# LAUNCHXL-F28377S_1.net
KiCad netlist of a schematic drawn in Altium Designer
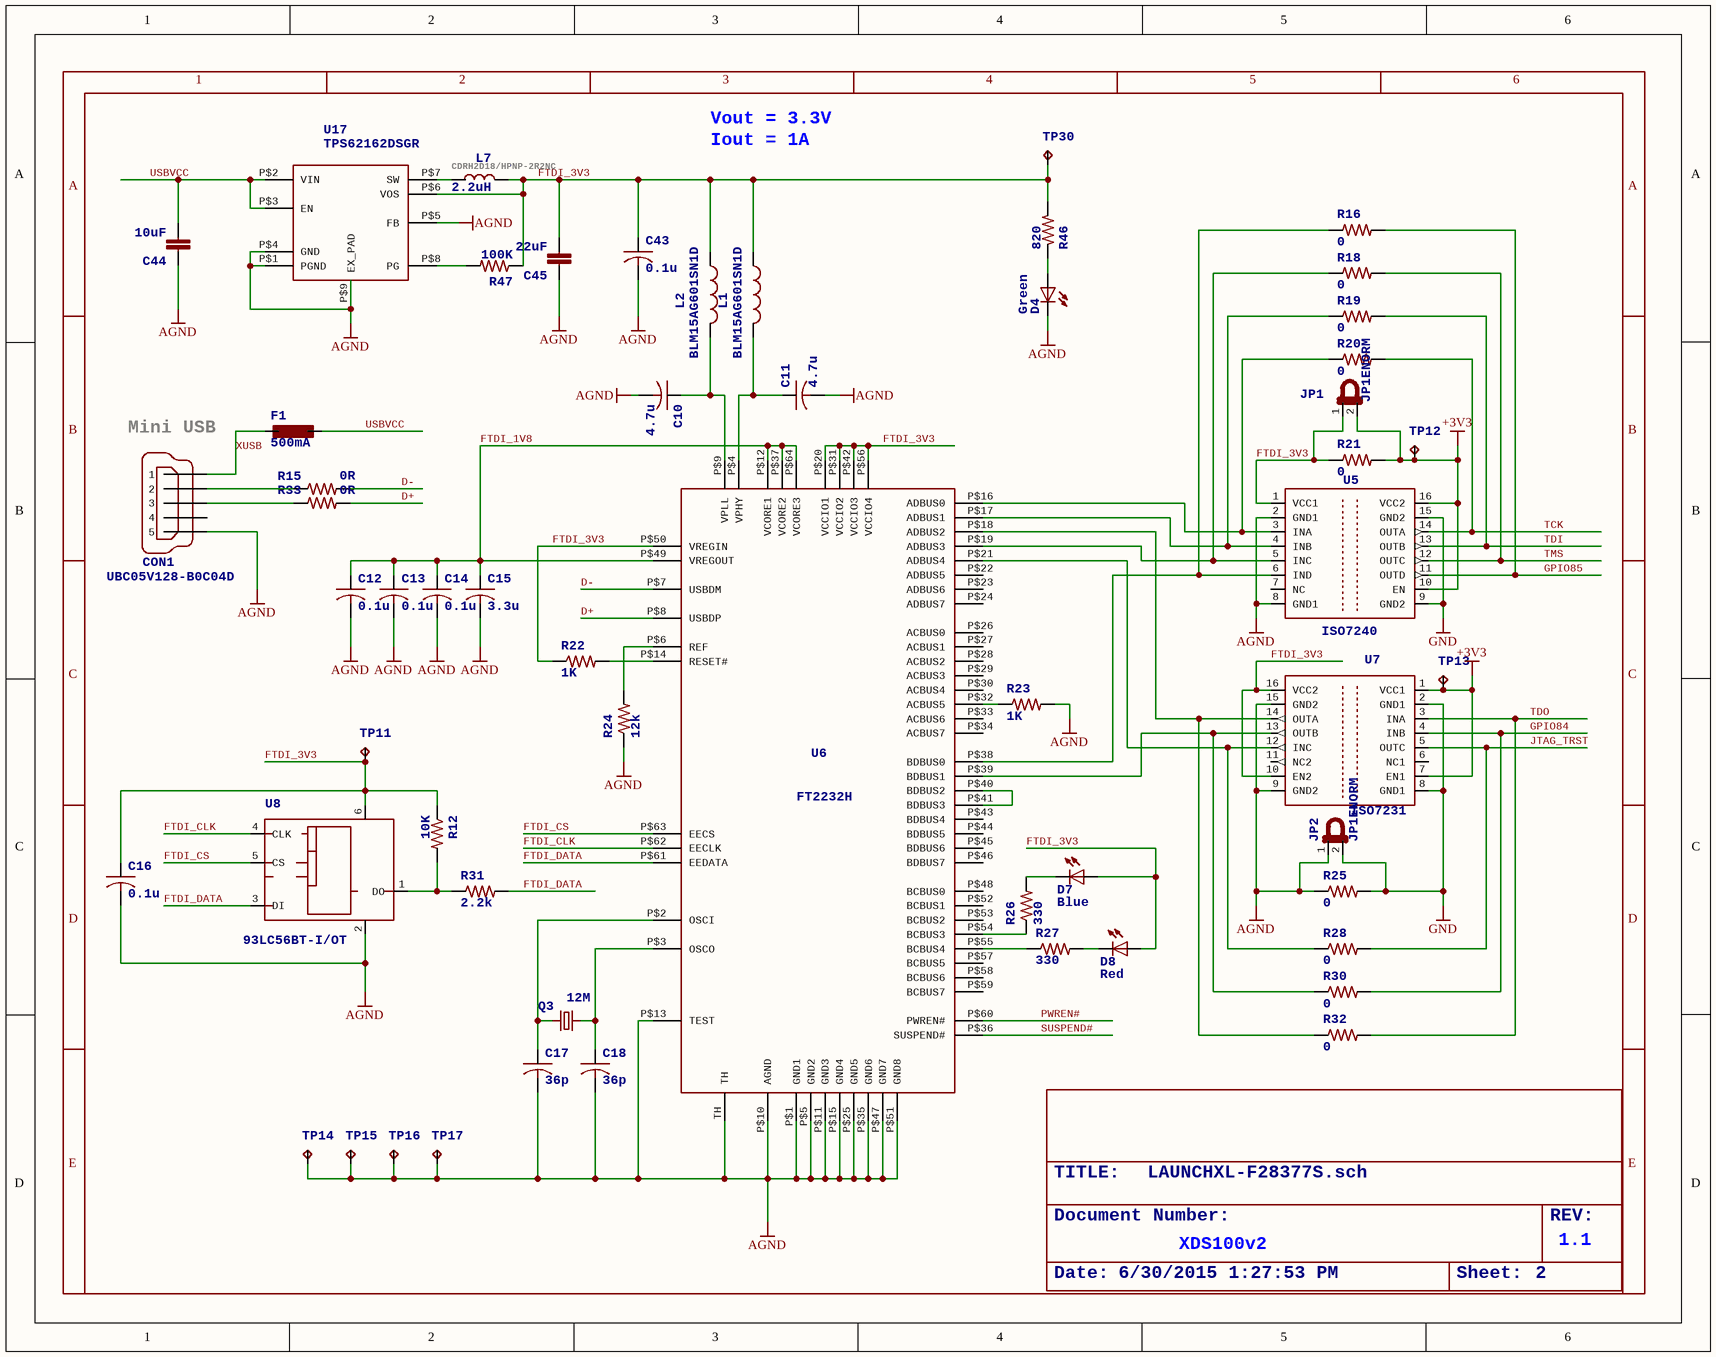
[diagram p0: LAUNCHXL-F28377S_1.SchDoc]

(export (version "E")
  (design (tool "Eeschema 10.0.6"))
  (components
    (comp (ref "C10")
      (value "4.7u")
      (footprint "C0402")
      (description "<B>CAPACITOR</B>, American symbol")
      (libsource (lib "rcl") (part "C-USC0402"))
    )
    (comp (ref "C11")
      (value "4.7u")
      (footprint "C0402")
      (description "<B>CAPACITOR</B>, American symbol")
      (libsource (lib "rcl") (part "C-USC0402"))
    )
    (comp (ref "C12")
      (value "0.1u")
      (footprint "C0402")
      (description "<B>CAPACITOR</B>, American symbol")
      (libsource (lib "rcl") (part "C-USC0402"))
    )
    (comp (ref "C13")
      (value "0.1u")
      (footprint "C0402")
      (description "<B>CAPACITOR</B>, American symbol")
      (libsource (lib "rcl") (part "C-USC0402"))
    )
    (comp (ref "C14")
      (value "0.1u")
      (footprint "C0402")
      (description "<B>CAPACITOR</B>, American symbol")
      (libsource (lib "rcl") (part "C-USC0402"))
    )
    (comp (ref "C15")
      (value "3.3u")
      (footprint "C0402")
      (description "<B>CAPACITOR</B>, American symbol")
      (libsource (lib "rcl") (part "C-USC0402"))
    )
    (comp (ref "C16")
      (value "0.1u")
      (footprint "C0402")
      (description "<B>CAPACITOR</B>, American symbol")
      (libsource (lib "rcl") (part "C-USC0402"))
    )
    (comp (ref "C17")
      (value "36p")
      (footprint "C0402")
      (description "<B>CAPACITOR</B>, American symbol")
      (libsource (lib "rcl") (part "C-USC0402"))
    )
    (comp (ref "C18")
      (value "36p")
      (footprint "C0402")
      (description "<B>CAPACITOR</B>, American symbol")
      (libsource (lib "rcl") (part "C-USC0402"))
    )
    (comp (ref "C43")
      (value "0.1u")
      (footprint "C0402")
      (description "<B>CAPACITOR</B>, American symbol")
      (libsource (lib "rcl") (part "C-USC0402"))
    )
    (comp (ref "C44")
      (value "10uF")
      (footprint "SPARKFUN_1210")
      (description "<b>Capacitor</b>\nStandard 0603 ceramic capacitor, and 0.1\" leaded capacitor.")
      (libsource (lib "RF430FRL152H_EVM_a") (part "SPARKFUN_CAP1210"))
    )
    (comp (ref "C45")
      (value "22uF")
      (footprint "SPARKFUN_1210")
      (description "<b>Capacitor</b>\nStandard 0603 ceramic capacitor, and 0.1\" leaded capacitor.")
      (libsource (lib "RF430FRL152H_EVM_a") (part "SPARKFUN_CAP1210"))
    )
    (comp (ref "CON1")
      (value "UBC05V128-B0C04D")
      (footprint "32005-201")
      (description "<b>MINI USB-B Conector</b><p>\nSource: www.cypressindustries.com")
      (libsource (lib "con-cypressindustries") (part "MINI-USB-32005-201"))
    )
    (comp (ref "D4")
      (value "Green")
      (footprint "CHIP-LED0603")
      (libsource (lib "led") (part "LEDCHIP-LED0603"))
    )
    (comp (ref "D7")
      (value "Blue")
      (footprint "CHIP-LED0603")
      (libsource (lib "led") (part "LEDCHIP-LED0603"))
    )
    (comp (ref "D8")
      (value "Red")
      (footprint "CHIP-LED0603")
      (libsource (lib "led") (part "LEDCHIP-LED0603"))
    )
    (comp (ref "F1")
      (value "500mA")
      (footprint "L1812")
      (description "<B>INDUCTOR</B>, European symbol")
      (libsource (lib "rcl") (part "L-EUL1812"))
    )
    (comp (ref "JP1")
      (value "JP1ENORM")
      (footprint "JP1")
      (description "<b>JUMPER</b>")
      (libsource (lib "jumper") (part "JP1ENORM"))
    )
    (comp (ref "JP2")
      (value "JP1ENORM")
      (footprint "JP1")
      (description "<b>JUMPER</b>")
      (libsource (lib "jumper") (part "JP1ENORM"))
    )
    (comp (ref "L1")
      (value "BLM15AG601SN1D")
      (footprint "R0402")
      (description "<B>INDUCTOR</B>, American symbol")
      (libsource (lib "rcl") (part "L-US0402"))
    )
    (comp (ref "L2")
      (value "BLM15AG601SN1D")
      (footprint "R0402")
      (description "<B>INDUCTOR</B>, American symbol")
      (libsource (lib "rcl") (part "L-US0402"))
    )
    (comp (ref "L7")
      (value "2.2uH")
      (footprint "INDUCT-3.2*3.2")
      (libsource (lib "LAUNCHXL-F28027") (part "VLF4012A`"))
    )
    (comp (ref "Q3")
      (value "12M")
      (footprint "HC49UP")
      (description "<b>CRYSTAL</b>")
      (libsource (lib "crystal") (part "CRYSTALHC49UP"))
    )
    (comp (ref "R12")
      (value "10K")
      (footprint "R0402")
      (description "<B>RESISTOR</B>, American symbol")
      (libsource (lib "rcl") (part "R-US_R0402"))
    )
    (comp (ref "R15")
      (value "0R")
      (footprint "R0402")
      (description "<B>RESISTOR</B>, American symbol")
      (libsource (lib "rcl") (part "R-US_R0402"))
    )
    (comp (ref "R16")
      (value "0")
      (footprint "R1206")
      (description "<B>RESISTOR</B>, American symbol")
      (libsource (lib "rcl") (part "R-US_R1206"))
    )
    (comp (ref "R18")
      (value "0")
      (footprint "R1206")
      (description "<B>RESISTOR</B>, American symbol")
      (libsource (lib "rcl") (part "R-US_R1206"))
    )
    (comp (ref "R19")
      (value "0")
      (footprint "R1206")
      (description "<B>RESISTOR</B>, American symbol")
      (libsource (lib "rcl") (part "R-US_R1206"))
    )
    (comp (ref "R20")
      (value "0")
      (footprint "R1206")
      (description "<B>RESISTOR</B>, American symbol")
      (libsource (lib "rcl") (part "R-US_R1206"))
    )
    (comp (ref "R21")
      (value "0")
      (footprint "R1206")
      (description "<B>RESISTOR</B>, American symbol")
      (libsource (lib "rcl") (part "R-US_R1206"))
    )
    (comp (ref "R22")
      (value "1K")
      (footprint "R0402")
      (description "<B>RESISTOR</B>, American symbol")
      (libsource (lib "rcl") (part "R-US_R0402"))
    )
    (comp (ref "R23")
      (value "1K")
      (footprint "R0402")
      (description "<B>RESISTOR</B>, American symbol")
      (libsource (lib "rcl") (part "R-US_R0402"))
    )
    (comp (ref "R24")
      (value "12k")
      (footprint "R0402")
      (description "<B>RESISTOR</B>, American symbol")
      (libsource (lib "rcl") (part "R-US_R0402"))
    )
    (comp (ref "R25")
      (value "0")
      (footprint "R1206")
      (description "<B>RESISTOR</B>, American symbol")
      (libsource (lib "rcl") (part "R-US_R1206"))
    )
    (comp (ref "R26")
      (value "330")
      (footprint "R0402")
      (description "<B>RESISTOR</B>, American symbol")
      (libsource (lib "rcl") (part "R-US_R0402"))
    )
    (comp (ref "R27")
      (value "330")
      (footprint "R0402")
      (description "<B>RESISTOR</B>, American symbol")
      (libsource (lib "rcl") (part "R-US_R0402"))
    )
    (comp (ref "R28")
      (value "0")
      (footprint "R1206")
      (description "<B>RESISTOR</B>, American symbol")
      (libsource (lib "rcl") (part "R-US_R1206"))
    )
    (comp (ref "R30")
      (value "0")
      (footprint "R1206")
      (description "<B>RESISTOR</B>, American symbol")
      (libsource (lib "rcl") (part "R-US_R1206"))
    )
    (comp (ref "R31")
      (value "2.2k")
      (footprint "R0402")
      (description "<B>RESISTOR</B>, American symbol")
      (libsource (lib "rcl") (part "R-US_R0402"))
    )
    (comp (ref "R32")
      (value "0")
      (footprint "R1206")
      (description "<B>RESISTOR</B>, American symbol")
      (libsource (lib "rcl") (part "R-US_R1206"))
    )
    (comp (ref "R33")
      (value "0R")
      (footprint "R0402")
      (description "<B>RESISTOR</B>, American symbol")
      (libsource (lib "rcl") (part "R-US_R0402"))
    )
    (comp (ref "R46")
      (value "820")
      (footprint "R0402")
      (description "<B>RESISTOR</B>, American symbol")
      (libsource (lib "rcl") (part "R-US_R0402"))
    )
    (comp (ref "R47")
      (value "100K")
      (footprint "R0402")
      (description "<B>RESISTOR</B>, American symbol")
      (libsource (lib "rcl") (part "R-US_R0402"))
    )
    (comp (ref "TP11")
      (value "TESTPAD_TPB1,27")
      (footprint "TESTPAD_B1,27")
      (description "<b>Test pad</b>")
      (libsource (lib "RF430FRL152H_EVM_a") (part "TESTPAD_TPB1,27"))
    )
    (comp (ref "TP12")
      (value "TESTPAD_TPB1,27")
      (footprint "TESTPAD_B1,27")
      (description "<b>Test pad</b>")
      (libsource (lib "RF430FRL152H_EVM_a") (part "TESTPAD_TPB1,27"))
    )
    (comp (ref "TP13")
      (value "TESTPAD_TPB1,27")
      (footprint "TESTPAD_B1,27")
      (description "<b>Test pad</b>")
      (libsource (lib "RF430FRL152H_EVM_a") (part "TESTPAD_TPB1,27"))
    )
    (comp (ref "TP14")
      (value "TESTPAD_TPB1,27")
      (footprint "TESTPAD_B1,27")
      (description "<b>Test pad</b>")
      (libsource (lib "RF430FRL152H_EVM_a") (part "TESTPAD_TPB1,27"))
    )
    (comp (ref "TP15")
      (value "TESTPAD_TPB1,27")
      (footprint "TESTPAD_B1,27")
      (description "<b>Test pad</b>")
      (libsource (lib "RF430FRL152H_EVM_a") (part "TESTPAD_TPB1,27"))
    )
    (comp (ref "TP16")
      (value "TESTPAD_TPB1,27")
      (footprint "TESTPAD_B1,27")
      (description "<b>Test pad</b>")
      (libsource (lib "RF430FRL152H_EVM_a") (part "TESTPAD_TPB1,27"))
    )
    (comp (ref "TP17")
      (value "TESTPAD_TPB1,27")
      (footprint "TESTPAD_B1,27")
      (description "<b>Test pad</b>")
      (libsource (lib "RF430FRL152H_EVM_a") (part "TESTPAD_TPB1,27"))
    )
    (comp (ref "TP30")
      (value "TESTPAD_TPB1,27")
      (footprint "TESTPAD_B1,27")
      (description "<b>Test pad</b>")
      (libsource (lib "RF430FRL152H_EVM_a") (part "TESTPAD_TPB1,27"))
    )
    (comp (ref "U$10")
      (value "ROY_JUMPER")
      (footprint "ROY_JUMPER")
      (libsource (lib "roy") (part "ROY_JUMPER"))
    )
    (comp (ref "U$11")
      (value "ROY_JUMPER")
      (footprint "ROY_JUMPER")
      (libsource (lib "roy") (part "ROY_JUMPER"))
    )
    (comp (ref "U5") (value "ISO7240") (footprint "SO-16DW") (libsource (lib "texas") (part "ISO7240")))
    (comp (ref "U6") (value "FT2232H") (footprint "QFN64") (libsource (lib "ti_trey") (part "FT2232H")))
    (comp (ref "U7") (value "ISO7231") (footprint "SO-16DW") (libsource (lib "texas") (part "ISO7231")))
    (comp (ref "U8")
      (value "93LC56BT-I/OT")
      (footprint "SOT23-6")
      (description "Serial <B>EPROM</B><p>\n1 K/2 K/4 K, low voltage, Microwire")
      (libsource (lib "ti_trey") (part "93*"))
    )
    (comp (ref "U17")
      (value "TPS62162DSGR")
      (footprint "TI_DSG8")
      (libsource (lib "LAUNCHXL-F28027") (part "TPS62162DSGR"))
    )
  )
  (nets
    (net (code "1") (name "+3V3") (class "Default")
      (node (ref "JP1") (pin "2") (pinfunction "2_2") (pintype "passive"))
      (node (ref "R21") (pin "2") (pinfunction "2_2") (pintype "passive"))
      (node (ref "TP12") (pin "TP") (pinfunction "TP_TP") (pintype "passive"))
      (node (ref "TP13") (pin "TP") (pinfunction "TP_TP") (pintype "passive"))
      (node (ref "U5") (pin "10") (pinfunction "EN_10") (pintype "passive"))
      (node (ref "U5") (pin "16") (pinfunction "VCC2_16") (pintype "power_in"))
      (node (ref "U7") (pin "1") (pinfunction "VCC1_1") (pintype "power_in"))
      (node (ref "U7") (pin "7") (pinfunction "EN1_7") (pintype "passive"))
    )
    (net (code "2") (name "/D+") (class "Default")
      (node (ref "R33") (pin "2") (pinfunction "2_2") (pintype "passive"))
      (node (ref "U6") (pin "P$8") (pinfunction "USBDP_P$8") (pintype "passive"))
    )
    (net (code "3") (name "/D-") (class "Default")
      (node (ref "R15") (pin "2") (pinfunction "2_2") (pintype "passive"))
      (node (ref "U6") (pin "P$7") (pinfunction "USBDM_P$7") (pintype "passive"))
    )
    (net (code "4") (name "/FTDI_1V8") (class "Default")
      (node (ref "C12") (pin "1") (pinfunction "1_1") (pintype "passive"))
      (node (ref "C13") (pin "1") (pinfunction "1_1") (pintype "passive"))
      (node (ref "C14") (pin "1") (pinfunction "1_1") (pintype "passive"))
      (node (ref "C15") (pin "1") (pinfunction "1_1") (pintype "passive"))
      (node (ref "U6") (pin "P$12") (pinfunction "VCORE1_P$12") (pintype "passive"))
      (node (ref "U6") (pin "P$37") (pinfunction "VCORE2_P$37") (pintype "passive"))
      (node (ref "U6") (pin "P$49") (pinfunction "VREGOUT_P$49") (pintype "passive"))
      (node (ref "U6") (pin "P$64") (pinfunction "VCORE3_P$64") (pintype "passive"))
    )
    (net (code "5") (name "/FTDI_3V3") (class "Default")
      (node (ref "C16") (pin "1") (pinfunction "1_1") (pintype "passive"))
      (node (ref "C43") (pin "1") (pinfunction "1_1") (pintype "passive"))
      (node (ref "C45") (pin "2") (pinfunction "2_2") (pintype "passive"))
      (node (ref "D7") (pin "A") (pinfunction "A_A") (pintype "passive"))
      (node (ref "D8") (pin "A") (pinfunction "A_A") (pintype "passive"))
      (node (ref "JP1") (pin "1") (pinfunction "1_1") (pintype "passive"))
      (node (ref "L1") (pin "1") (pinfunction "1_1") (pintype "passive"))
      (node (ref "L2") (pin "1") (pinfunction "1_1") (pintype "passive"))
      (node (ref "L7") (pin "P$1") (pinfunction "1_P$1") (pintype "passive"))
      (node (ref "R12") (pin "1") (pinfunction "1_1") (pintype "passive"))
      (node (ref "R21") (pin "1") (pinfunction "1_1") (pintype "passive"))
      (node (ref "R22") (pin "1") (pinfunction "1_1") (pintype "passive"))
      (node (ref "R46") (pin "2") (pinfunction "2_2") (pintype "passive"))
      (node (ref "R47") (pin "1") (pinfunction "1_1") (pintype "passive"))
      (node (ref "TP11") (pin "TP") (pinfunction "TP_TP") (pintype "passive"))
      (node (ref "TP30") (pin "TP") (pinfunction "TP_TP") (pintype "passive"))
      (node (ref "U17") (pin "P$6") (pinfunction "VOS_P$6") (pintype "passive"))
      (node (ref "U5") (pin "1") (pinfunction "VCC1_1") (pintype "power_in"))
      (node (ref "U6") (pin "P$20") (pinfunction "VCCIO1_P$20") (pintype "passive"))
      (node (ref "U6") (pin "P$31") (pinfunction "VCCIO2_P$31") (pintype "passive"))
      (node (ref "U6") (pin "P$42") (pinfunction "VCCIO3_P$42") (pintype "passive"))
      (node (ref "U6") (pin "P$50") (pinfunction "VREGIN_P$50") (pintype "passive"))
      (node (ref "U6") (pin "P$56") (pinfunction "VCCIO4_P$56") (pintype "passive"))
      (node (ref "U7") (pin "10") (pinfunction "EN2_10") (pintype "passive"))
      (node (ref "U7") (pin "16") (pinfunction "VCC2_16") (pintype "power_in"))
      (node (ref "U8") (pin "6") (pinfunction "VCC_6") (pintype "power_in"))
    )
    (net (code "6") (name "/FTDI_CLK") (class "Default")
      (node (ref "U6") (pin "P$62") (pinfunction "EECLK_P$62") (pintype "passive"))
      (node (ref "U8") (pin "4") (pinfunction "CLK_4") (pintype "passive"))
    )
    (net (code "7") (name "/FTDI_CS") (class "Default")
      (node (ref "U6") (pin "P$63") (pinfunction "EECS_P$63") (pintype "passive"))
      (node (ref "U8") (pin "5") (pinfunction "CS_5") (pintype "passive"))
    )
    (net (code "8") (name "/FTDI_DATA") (class "Default")
      (node (ref "R31") (pin "2") (pinfunction "2_2") (pintype "passive"))
      (node (ref "U6") (pin "P$61") (pinfunction "EEDATA_P$61") (pintype "passive"))
      (node (ref "U8") (pin "3") (pinfunction "DI_3") (pintype "passive"))
    )
    (net (code "9") (name "/GPIO84") (class "Default")
      (node (ref "R30") (pin "2") (pinfunction "2_2") (pintype "passive"))
      (node (ref "U7") (pin "4") (pinfunction "INB_4") (pintype "passive"))
    )
    (net (code "10") (name "/GPIO85") (class "Default")
      (node (ref "R16") (pin "2") (pinfunction "2_2") (pintype "passive"))
      (node (ref "U5") (pin "11") (pinfunction "OUTD_11") (pintype "output"))
    )
    (net (code "11") (name "/JTAG_TRST") (class "Default")
      (node (ref "R28") (pin "2") (pinfunction "2_2") (pintype "passive"))
      (node (ref "U7") (pin "5") (pinfunction "OUTC_5") (pintype "passive"))
    )
    (net (code "12") (name "/PWREN#") (class "Default")
      (node (ref "U6") (pin "P$60") (pinfunction "PWREN#_P$60") (pintype "passive"))
    )
    (net (code "13") (name "/SUSPEND#") (class "Default")
      (node (ref "U6") (pin "P$36") (pinfunction "SUSPEND#_P$36") (pintype "passive"))
    )
    (net (code "14") (name "/TCK") (class "Default")
      (node (ref "R20") (pin "2") (pinfunction "2_2") (pintype "passive"))
      (node (ref "U5") (pin "14") (pinfunction "OUTA_14") (pintype "output"))
    )
    (net (code "15") (name "/TDI") (class "Default")
      (node (ref "R19") (pin "2") (pinfunction "2_2") (pintype "passive"))
      (node (ref "U5") (pin "13") (pinfunction "OUTB_13") (pintype "output"))
    )
    (net (code "16") (name "/TDO") (class "Default")
      (node (ref "R32") (pin "2") (pinfunction "2_2") (pintype "passive"))
      (node (ref "U7") (pin "3") (pinfunction "INA_3") (pintype "passive"))
    )
    (net (code "17") (name "/TMS") (class "Default")
      (node (ref "R18") (pin "2") (pinfunction "2_2") (pintype "passive"))
      (node (ref "U5") (pin "12") (pinfunction "OUTC_12") (pintype "output"))
    )
    (net (code "18") (name "/USBVCC") (class "Default")
      (node (ref "C44") (pin "2") (pinfunction "2_2") (pintype "passive"))
      (node (ref "F1") (pin "1") (pinfunction "1_1") (pintype "passive"))
      (node (ref "U17") (pin "P$2") (pinfunction "VIN_P$2") (pintype "passive"))
      (node (ref "U17") (pin "P$3") (pinfunction "EN_P$3") (pintype "passive"))
    )
    (net (code "19") (name "/XUSB") (class "Default")
      (node (ref "CON1") (pin "1") (pinfunction "1_1") (pintype "passive"))
      (node (ref "F1") (pin "2") (pinfunction "2_2") (pintype "passive"))
    )
    (net (code "20") (name "AGND") (class "Default")
      (node (ref "C10") (pin "2") (pinfunction "2_2") (pintype "passive"))
      (node (ref "C11") (pin "2") (pinfunction "2_2") (pintype "passive"))
      (node (ref "C12") (pin "2") (pinfunction "2_2") (pintype "passive"))
      (node (ref "C13") (pin "2") (pinfunction "2_2") (pintype "passive"))
      (node (ref "C14") (pin "2") (pinfunction "2_2") (pintype "passive"))
      (node (ref "C15") (pin "2") (pinfunction "2_2") (pintype "passive"))
      (node (ref "C16") (pin "2") (pinfunction "2_2") (pintype "passive"))
      (node (ref "C17") (pin "2") (pinfunction "2_2") (pintype "passive"))
      (node (ref "C18") (pin "2") (pinfunction "2_2") (pintype "passive"))
      (node (ref "C43") (pin "2") (pinfunction "2_2") (pintype "passive"))
      (node (ref "C44") (pin "1") (pinfunction "1_1") (pintype "passive"))
      (node (ref "C45") (pin "1") (pinfunction "1_1") (pintype "passive"))
      (node (ref "CON1") (pin "5") (pinfunction "5_5") (pintype "passive"))
      (node (ref "D4") (pin "C") (pinfunction "C_C") (pintype "passive"))
      (node (ref "JP2") (pin "1") (pinfunction "1_1") (pintype "passive"))
      (node (ref "R23") (pin "2") (pinfunction "2_2") (pintype "passive"))
      (node (ref "R24") (pin "1") (pinfunction "1_1") (pintype "passive"))
      (node (ref "R25") (pin "1") (pinfunction "1_1") (pintype "passive"))
      (node (ref "TP14") (pin "TP") (pinfunction "TP_TP") (pintype "passive"))
      (node (ref "TP15") (pin "TP") (pinfunction "TP_TP") (pintype "passive"))
      (node (ref "TP16") (pin "TP") (pinfunction "TP_TP") (pintype "passive"))
      (node (ref "TP17") (pin "TP") (pinfunction "TP_TP") (pintype "passive"))
      (node (ref "U17") (pin "P$1") (pinfunction "PGND_P$1") (pintype "passive"))
      (node (ref "U17") (pin "P$4") (pinfunction "GND_P$4") (pintype "passive"))
      (node (ref "U17") (pin "P$5") (pinfunction "FB_P$5") (pintype "passive"))
      (node (ref "U17") (pin "P$9") (pinfunction "EX_PAD_P$9") (pintype "passive"))
      (node (ref "U5") (pin "2") (pinfunction "GND1_2") (pintype "power_in"))
      (node (ref "U5") (pin "8") (pinfunction "GND1_8") (pintype "power_in"))
      (node (ref "U6") (pin "P$1") (pinfunction "GND1_P$1") (pintype "passive"))
      (node (ref "U6") (pin "P$10") (pinfunction "AGND_P$10") (pintype "passive"))
      (node (ref "U6") (pin "P$11") (pinfunction "GND3_P$11") (pintype "passive"))
      (node (ref "U6") (pin "P$13") (pinfunction "TEST_P$13") (pintype "passive"))
      (node (ref "U6") (pin "P$15") (pinfunction "GND4_P$15") (pintype "passive"))
      (node (ref "U6") (pin "P$25") (pinfunction "GND5_P$25") (pintype "passive"))
      (node (ref "U6") (pin "P$35") (pinfunction "GND6_P$35") (pintype "passive"))
      (node (ref "U6") (pin "P$47") (pinfunction "GND7_P$47") (pintype "passive"))
      (node (ref "U6") (pin "P$5") (pinfunction "GND2_P$5") (pintype "passive"))
      (node (ref "U6") (pin "P$51") (pinfunction "GND8_P$51") (pintype "passive"))
      (node (ref "U6") (pin "TH") (pinfunction "TH_TH") (pintype "passive"))
      (node (ref "U7") (pin "15") (pinfunction "GND2_15") (pintype "power_in"))
      (node (ref "U7") (pin "9") (pinfunction "GND2_9") (pintype "power_in"))
      (node (ref "U8") (pin "2") (pinfunction "GND_2") (pintype "power_in"))
    )
    (net (code "21") (name "GND") (class "Default")
      (node (ref "JP2") (pin "2") (pinfunction "2_2") (pintype "passive"))
      (node (ref "R25") (pin "2") (pinfunction "2_2") (pintype "passive"))
      (node (ref "U5") (pin "15") (pinfunction "GND2_15") (pintype "power_in"))
      (node (ref "U5") (pin "9") (pinfunction "GND2_9") (pintype "power_in"))
      (node (ref "U7") (pin "2") (pinfunction "GND1_2") (pintype "power_in"))
      (node (ref "U7") (pin "8") (pinfunction "GND1_8") (pintype "power_in"))
    )
    (net (code "22") (name "Net-(CON1-Pad2)") (class "Default")
      (node (ref "CON1") (pin "2") (pinfunction "2_2") (pintype "passive"))
      (node (ref "R15") (pin "1") (pinfunction "1_1") (pintype "passive"))
    )
    (net (code "23") (name "Net-(CON1-Pad3)") (class "Default")
      (node (ref "CON1") (pin "3") (pinfunction "3_3") (pintype "passive"))
      (node (ref "R33") (pin "1") (pinfunction "1_1") (pintype "passive"))
    )
    (net (code "24") (name "Net-(D4-PadA)") (class "Default")
      (node (ref "D4") (pin "A") (pinfunction "A_A") (pintype "passive"))
      (node (ref "R46") (pin "1") (pinfunction "1_1") (pintype "passive"))
    )
    (net (code "25") (name "Net-(D7-PadC)") (class "Default")
      (node (ref "D7") (pin "C") (pinfunction "C_C") (pintype "passive"))
      (node (ref "R26") (pin "2") (pinfunction "2_2") (pintype "passive"))
    )
    (net (code "26") (name "Net-(D8-PadC)") (class "Default")
      (node (ref "D8") (pin "C") (pinfunction "C_C") (pintype "passive"))
      (node (ref "R27") (pin "2") (pinfunction "2_2") (pintype "passive"))
    )
    (net (code "27") (name "Net-(L7-2)") (class "Default")
      (node (ref "L7") (pin "P$2") (pinfunction "2_P$2") (pintype "passive"))
      (node (ref "U17") (pin "P$7") (pinfunction "SW_P$7") (pintype "passive"))
    )
    (net (code "28") (name "Net-(U5-INA)") (class "Default")
      (node (ref "R20") (pin "1") (pinfunction "1_1") (pintype "passive"))
      (node (ref "U5") (pin "3") (pinfunction "INA_3") (pintype "passive"))
      (node (ref "U6") (pin "P$16") (pinfunction "ADBUS0_P$16") (pintype "passive"))
    )
    (net (code "29") (name "Net-(U5-INB)") (class "Default")
      (node (ref "R19") (pin "1") (pinfunction "1_1") (pintype "passive"))
      (node (ref "U5") (pin "4") (pinfunction "INB_4") (pintype "passive"))
      (node (ref "U6") (pin "P$17") (pinfunction "ADBUS1_P$17") (pintype "passive"))
    )
    (net (code "30") (name "Net-(U5-INC)") (class "Default")
      (node (ref "R18") (pin "1") (pinfunction "1_1") (pintype "passive"))
      (node (ref "U5") (pin "5") (pinfunction "INC_5") (pintype "passive"))
      (node (ref "U6") (pin "P$19") (pinfunction "ADBUS3_P$19") (pintype "passive"))
    )
    (net (code "31") (name "Net-(U5-IND)") (class "Default")
      (node (ref "R16") (pin "1") (pinfunction "1_1") (pintype "passive"))
      (node (ref "U5") (pin "6") (pinfunction "IND_6") (pintype "passive"))
      (node (ref "U6") (pin "P$38") (pinfunction "BDBUS0_P$38") (pintype "passive"))
    )
    (net (code "32") (name "Net-(U6-ACBUS5)") (class "Default")
      (node (ref "R23") (pin "1") (pinfunction "1_1") (pintype "passive"))
      (node (ref "U6") (pin "P$32") (pinfunction "ACBUS5_P$32") (pintype "passive"))
    )
    (net (code "33") (name "Net-(U6-ADBUS2)") (class "Default")
      (node (ref "R32") (pin "1") (pinfunction "1_1") (pintype "passive"))
      (node (ref "U6") (pin "P$18") (pinfunction "ADBUS2_P$18") (pintype "passive"))
      (node (ref "U7") (pin "14") (pinfunction "OUTA_14") (pintype "output"))
    )
    (net (code "34") (name "Net-(U6-ADBUS4)") (class "Default")
      (node (ref "R28") (pin "1") (pinfunction "1_1") (pintype "passive"))
      (node (ref "U6") (pin "P$21") (pinfunction "ADBUS4_P$21") (pintype "passive"))
      (node (ref "U7") (pin "12") (pinfunction "INC_12") (pintype "output"))
    )
    (net (code "35") (name "Net-(U6-BCBUS3)") (class "Default")
      (node (ref "R26") (pin "1") (pinfunction "1_1") (pintype "passive"))
      (node (ref "U6") (pin "P$54") (pinfunction "BCBUS3_P$54") (pintype "passive"))
    )
    (net (code "36") (name "Net-(U6-BCBUS4)") (class "Default")
      (node (ref "R27") (pin "1") (pinfunction "1_1") (pintype "passive"))
      (node (ref "U6") (pin "P$55") (pinfunction "BCBUS4_P$55") (pintype "passive"))
    )
    (net (code "37") (name "Net-(U6-BDBUS1)") (class "Default")
      (node (ref "R30") (pin "1") (pinfunction "1_1") (pintype "passive"))
      (node (ref "U6") (pin "P$39") (pinfunction "BDBUS1_P$39") (pintype "passive"))
      (node (ref "U7") (pin "13") (pinfunction "OUTB_13") (pintype "output"))
    )
    (net (code "38") (name "Net-(U6-BDBUS2)") (class "Default")
      (node (ref "U6") (pin "P$40") (pinfunction "BDBUS2_P$40") (pintype "passive"))
      (node (ref "U6") (pin "P$41") (pinfunction "BDBUS3_P$41") (pintype "passive"))
    )
    (net (code "39") (name "Net-(U6-OSCI)") (class "Default")
      (node (ref "C17") (pin "1") (pinfunction "1_1") (pintype "passive"))
      (node (ref "Q3") (pin "1") (pinfunction "1_1") (pintype "passive"))
      (node (ref "U6") (pin "P$2") (pinfunction "OSCI_P$2") (pintype "passive"))
    )
    (net (code "40") (name "Net-(U6-OSCO)") (class "Default")
      (node (ref "C18") (pin "1") (pinfunction "1_1") (pintype "passive"))
      (node (ref "Q3") (pin "2") (pinfunction "2_2") (pintype "passive"))
      (node (ref "U6") (pin "P$3") (pinfunction "OSCO_P$3") (pintype "passive"))
    )
    (net (code "41") (name "Net-(U6-REF)") (class "Default")
      (node (ref "R24") (pin "2") (pinfunction "2_2") (pintype "passive"))
      (node (ref "U6") (pin "P$6") (pinfunction "REF_P$6") (pintype "passive"))
    )
    (net (code "42") (name "Net-(U6-RESET#)") (class "Default")
      (node (ref "R22") (pin "2") (pinfunction "2_2") (pintype "passive"))
      (node (ref "U6") (pin "P$14") (pinfunction "RESET#_P$14") (pintype "passive"))
    )
    (net (code "43") (name "Net-(U6-VPHY)") (class "Default")
      (node (ref "C11") (pin "1") (pinfunction "1_1") (pintype "passive"))
      (node (ref "L1") (pin "2") (pinfunction "2_2") (pintype "passive"))
      (node (ref "U6") (pin "P$4") (pinfunction "VPHY_P$4") (pintype "passive"))
    )
    (net (code "44") (name "Net-(U6-VPLL)") (class "Default")
      (node (ref "C10") (pin "1") (pinfunction "1_1") (pintype "passive"))
      (node (ref "L2") (pin "2") (pinfunction "2_2") (pintype "passive"))
      (node (ref "U6") (pin "P$9") (pinfunction "VPLL_P$9") (pintype "passive"))
    )
    (net (code "45") (name "Net-(U8-DO)") (class "Default")
      (node (ref "R12") (pin "2") (pinfunction "2_2") (pintype "passive"))
      (node (ref "R31") (pin "1") (pinfunction "1_1") (pintype "passive"))
      (node (ref "U8") (pin "1") (pinfunction "DO_1") (pintype "tri_state"))
    )
    (net (code "46") (name "Net-(U17-PG)") (class "Default")
      (node (ref "R47") (pin "2") (pinfunction "2_2") (pintype "passive"))
      (node (ref "U17") (pin "P$8") (pinfunction "PG_P$8") (pintype "passive"))
    )
    (net (code "47") (name "unconnected-(CON1-Pad4)") (class "Default")
      (node (ref "CON1") (pin "4") (pinfunction "4_4") (pintype "passive"))
    )
    (net (code "48") (name "unconnected-(U5-NC-Pad7)") (class "Default")
      (node (ref "U5") (pin "7") (pinfunction "NC_7") (pintype "passive"))
    )
    (net (code "49") (name "unconnected-(U6-ACBUS0-PadP$26)") (class "Default")
      (node (ref "U6") (pin "P$26") (pinfunction "ACBUS0_P$26") (pintype "passive"))
    )
    (net (code "50") (name "unconnected-(U6-ACBUS1-PadP$27)") (class "Default")
      (node (ref "U6") (pin "P$27") (pinfunction "ACBUS1_P$27") (pintype "passive"))
    )
    (net (code "51") (name "unconnected-(U6-ACBUS2-PadP$28)") (class "Default")
      (node (ref "U6") (pin "P$28") (pinfunction "ACBUS2_P$28") (pintype "passive"))
    )
    (net (code "52") (name "unconnected-(U6-ACBUS3-PadP$29)") (class "Default")
      (node (ref "U6") (pin "P$29") (pinfunction "ACBUS3_P$29") (pintype "passive"))
    )
    (net (code "53") (name "unconnected-(U6-ACBUS4-PadP$30)") (class "Default")
      (node (ref "U6") (pin "P$30") (pinfunction "ACBUS4_P$30") (pintype "passive"))
    )
    (net (code "54") (name "unconnected-(U6-ACBUS6-PadP$33)") (class "Default")
      (node (ref "U6") (pin "P$33") (pinfunction "ACBUS6_P$33") (pintype "passive"))
    )
    (net (code "55") (name "unconnected-(U6-ACBUS7-PadP$34)") (class "Default")
      (node (ref "U6") (pin "P$34") (pinfunction "ACBUS7_P$34") (pintype "passive"))
    )
    (net (code "56") (name "unconnected-(U6-ADBUS5-PadP$22)") (class "Default")
      (node (ref "U6") (pin "P$22") (pinfunction "ADBUS5_P$22") (pintype "passive"))
    )
    (net (code "57") (name "unconnected-(U6-ADBUS6-PadP$23)") (class "Default")
      (node (ref "U6") (pin "P$23") (pinfunction "ADBUS6_P$23") (pintype "passive"))
    )
    (net (code "58") (name "unconnected-(U6-ADBUS7-PadP$24)") (class "Default")
      (node (ref "U6") (pin "P$24") (pinfunction "ADBUS7_P$24") (pintype "passive"))
    )
    (net (code "59") (name "unconnected-(U6-BCBUS0-PadP$48)") (class "Default")
      (node (ref "U6") (pin "P$48") (pinfunction "BCBUS0_P$48") (pintype "passive"))
    )
    (net (code "60") (name "unconnected-(U6-BCBUS1-PadP$52)") (class "Default")
      (node (ref "U6") (pin "P$52") (pinfunction "BCBUS1_P$52") (pintype "passive"))
    )
    (net (code "61") (name "unconnected-(U6-BCBUS2-PadP$53)") (class "Default")
      (node (ref "U6") (pin "P$53") (pinfunction "BCBUS2_P$53") (pintype "passive"))
    )
    (net (code "62") (name "unconnected-(U6-BCBUS5-PadP$57)") (class "Default")
      (node (ref "U6") (pin "P$57") (pinfunction "BCBUS5_P$57") (pintype "passive"))
    )
    (net (code "63") (name "unconnected-(U6-BCBUS6-PadP$58)") (class "Default")
      (node (ref "U6") (pin "P$58") (pinfunction "BCBUS6_P$58") (pintype "passive"))
    )
    (net (code "64") (name "unconnected-(U6-BCBUS7-PadP$59)") (class "Default")
      (node (ref "U6") (pin "P$59") (pinfunction "BCBUS7_P$59") (pintype "passive"))
    )
    (net (code "65") (name "unconnected-(U6-BDBUS4-PadP$43)") (class "Default")
      (node (ref "U6") (pin "P$43") (pinfunction "BDBUS4_P$43") (pintype "passive"))
    )
    (net (code "66") (name "unconnected-(U6-BDBUS5-PadP$44)") (class "Default")
      (node (ref "U6") (pin "P$44") (pinfunction "BDBUS5_P$44") (pintype "passive"))
    )
    (net (code "67") (name "unconnected-(U6-BDBUS6-PadP$45)") (class "Default")
      (node (ref "U6") (pin "P$45") (pinfunction "BDBUS6_P$45") (pintype "passive"))
    )
    (net (code "68") (name "unconnected-(U6-BDBUS7-PadP$46)") (class "Default")
      (node (ref "U6") (pin "P$46") (pinfunction "BDBUS7_P$46") (pintype "passive"))
    )
    (net (code "69") (name "unconnected-(U7-NC1-Pad6)") (class "Default")
      (node (ref "U7") (pin "6") (pinfunction "NC1_6") (pintype "passive"))
    )
    (net (code "70") (name "unconnected-(U7-NC2-Pad11)") (class "Default")
      (node (ref "U7") (pin "11") (pinfunction "NC2_11") (pintype "output"))
    )
  )
)
